# single-spi-interface.net
KiCad netlist of a schematic drawn in EAGLE
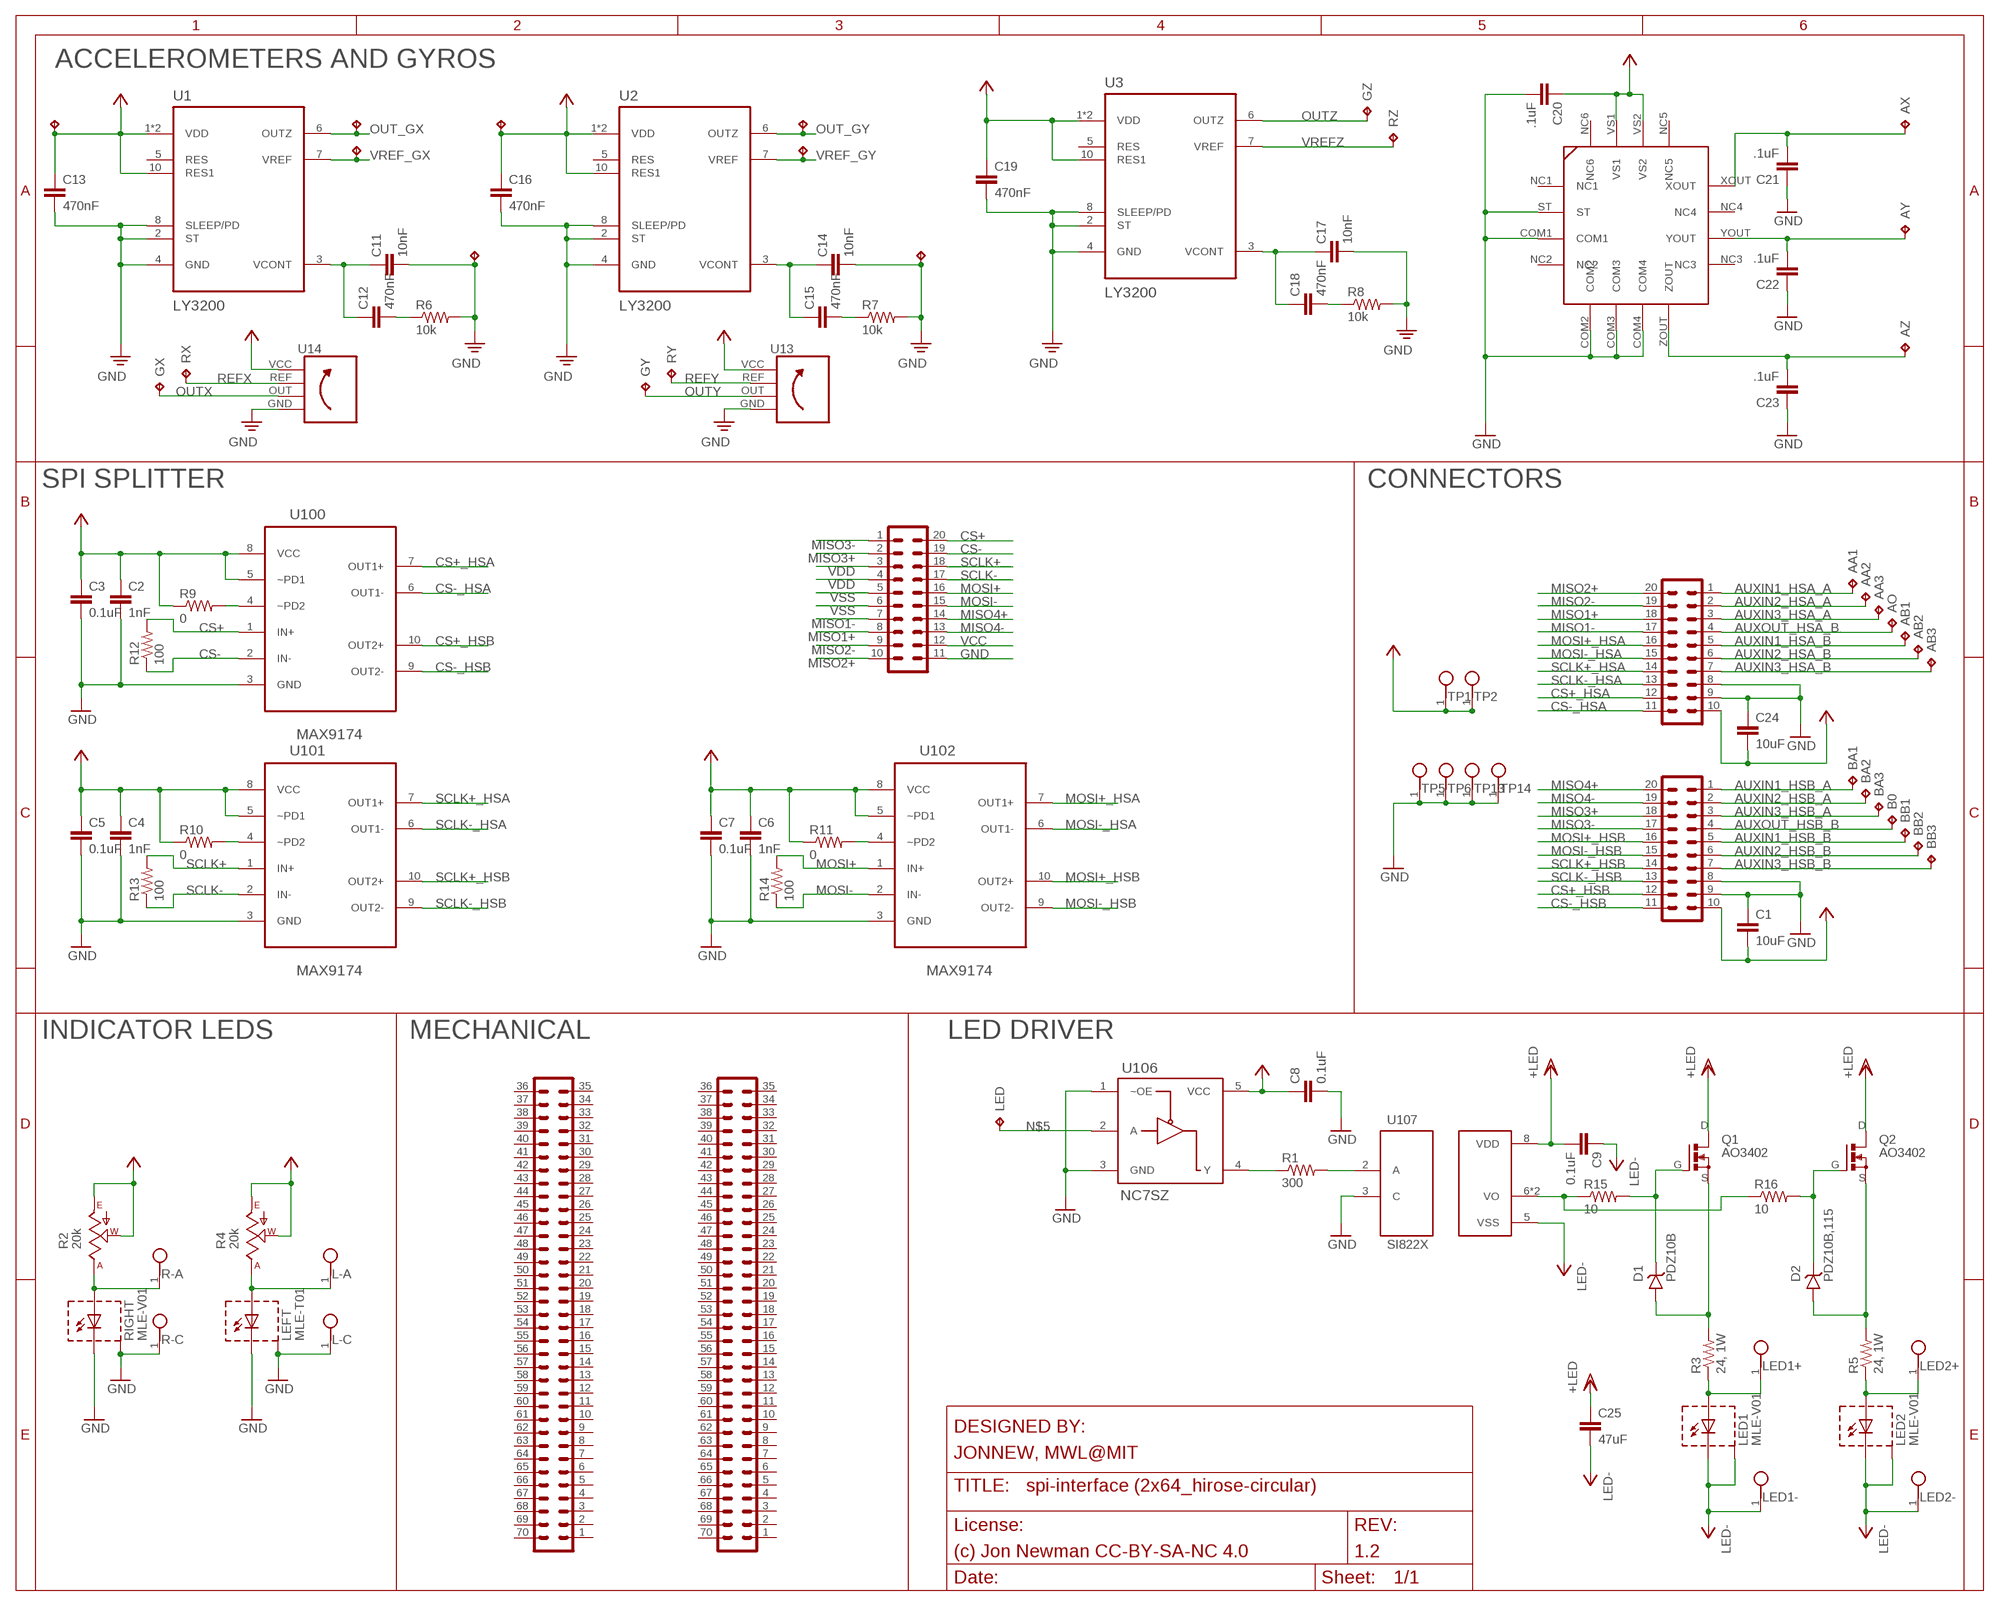
[diagram p0: schematic, sheet 1]

(export (version "E")
  (design (tool "Eeschema 10.0.6"))
  (components
    (comp (ref "AA1")
      (value "TP_0.5MM")
      (footprint "eagle-import:TESTPOINT_0.5MM")
      (libsource (lib "eagle-import") (part "TP_0.5MM"))
    )
    (comp (ref "AA2")
      (value "TP_0.5MM")
      (footprint "eagle-import:TESTPOINT_0.5MM")
      (libsource (lib "eagle-import") (part "TP_0.5MM"))
    )
    (comp (ref "AA3")
      (value "TP_0.5MM")
      (footprint "eagle-import:TESTPOINT_0.5MM")
      (libsource (lib "eagle-import") (part "TP_0.5MM"))
    )
    (comp (ref "AB1")
      (value "TP_0.5MM")
      (footprint "eagle-import:TESTPOINT_0.5MM")
      (libsource (lib "eagle-import") (part "TP_0.5MM"))
    )
    (comp (ref "AB2")
      (value "TP_0.5MM")
      (footprint "eagle-import:TESTPOINT_0.5MM")
      (libsource (lib "eagle-import") (part "TP_0.5MM"))
    )
    (comp (ref "AB3")
      (value "TP_0.5MM")
      (footprint "eagle-import:TESTPOINT_0.5MM")
      (libsource (lib "eagle-import") (part "TP_0.5MM"))
    )
    (comp (ref "AO")
      (value "TP_0.5MM")
      (footprint "eagle-import:TESTPOINT_0.5MM")
      (libsource (lib "eagle-import") (part "TP_0.5MM"))
    )
    (comp (ref "AX")
      (value "TP_0.5MM")
      (footprint "eagle-import:TESTPOINT_0.5MM")
      (libsource (lib "eagle-import") (part "TP_0.5MM"))
    )
    (comp (ref "AY")
      (value "TP_0.5MM")
      (footprint "eagle-import:TESTPOINT_0.5MM")
      (libsource (lib "eagle-import") (part "TP_0.5MM"))
    )
    (comp (ref "AZ")
      (value "TP_0.5MM")
      (footprint "eagle-import:TESTPOINT_0.5MM")
      (libsource (lib "eagle-import") (part "TP_0.5MM"))
    )
    (comp (ref "B0")
      (value "TP_0.5MM")
      (footprint "eagle-import:TESTPOINT_0.5MM")
      (libsource (lib "eagle-import") (part "TP_0.5MM"))
    )
    (comp (ref "BA1")
      (value "TP_0.5MM")
      (footprint "eagle-import:TESTPOINT_0.5MM")
      (libsource (lib "eagle-import") (part "TP_0.5MM"))
    )
    (comp (ref "BA2")
      (value "TP_0.5MM")
      (footprint "eagle-import:TESTPOINT_0.5MM")
      (libsource (lib "eagle-import") (part "TP_0.5MM"))
    )
    (comp (ref "BA3")
      (value "TP_0.5MM")
      (footprint "eagle-import:TESTPOINT_0.5MM")
      (libsource (lib "eagle-import") (part "TP_0.5MM"))
    )
    (comp (ref "BB1")
      (value "TP_0.5MM")
      (footprint "eagle-import:TESTPOINT_0.5MM")
      (libsource (lib "eagle-import") (part "TP_0.5MM"))
    )
    (comp (ref "BB2")
      (value "TP_0.5MM")
      (footprint "eagle-import:TESTPOINT_0.5MM")
      (libsource (lib "eagle-import") (part "TP_0.5MM"))
    )
    (comp (ref "BB3")
      (value "TP_0.5MM")
      (footprint "eagle-import:TESTPOINT_0.5MM")
      (libsource (lib "eagle-import") (part "TP_0.5MM"))
    )
    (comp (ref "C1")
      (value "10uF")
      (footprint "eagle-import:0805")
      (fields (field (name "PARTNO") "C2012X5R1Cxxxxxxx"))
      (libsource (lib "eagle-import") (part "C_0805"))
    )
    (comp (ref "C2")
      (value "1nF")
      (footprint "eagle-import:0201")
      (libsource (lib "eagle-import") (part "jonnew_C_0201"))
    )
    (comp (ref "C3")
      (value "0.1uF")
      (footprint "eagle-import:0402")
      (libsource (lib "eagle-import") (part "jonnew_C_0402"))
    )
    (comp (ref "C4")
      (value "1nF")
      (footprint "eagle-import:0201")
      (libsource (lib "eagle-import") (part "jonnew_C_0201"))
    )
    (comp (ref "C5")
      (value "0.1uF")
      (footprint "eagle-import:0402")
      (libsource (lib "eagle-import") (part "jonnew_C_0402"))
    )
    (comp (ref "C6")
      (value "1nF")
      (footprint "eagle-import:0201")
      (libsource (lib "eagle-import") (part "jonnew_C_0201"))
    )
    (comp (ref "C7")
      (value "0.1uF")
      (footprint "eagle-import:0402")
      (libsource (lib "eagle-import") (part "jonnew_C_0402"))
    )
    (comp (ref "C8")
      (value "0.1uF")
      (footprint "eagle-import:0402")
      (libsource (lib "eagle-import") (part "jonnew_C_0402"))
    )
    (comp (ref "C9")
      (value "0.1uF")
      (footprint "eagle-import:0402")
      (libsource (lib "eagle-import") (part "jonnew_C_0402"))
    )
    (comp (ref "C11")
      (value "10nF")
      (footprint "eagle-import:0201")
      (libsource (lib "eagle-import") (part "jonnew_C_0201"))
    )
    (comp (ref "C12")
      (value "470nF")
      (footprint "eagle-import:0201")
      (libsource (lib "eagle-import") (part "jonnew_C_0201"))
    )
    (comp (ref "C13")
      (value "470nF")
      (footprint "eagle-import:0201")
      (libsource (lib "eagle-import") (part "jonnew_C_0201"))
    )
    (comp (ref "C14")
      (value "10nF")
      (footprint "eagle-import:0201")
      (libsource (lib "eagle-import") (part "jonnew_C_0201"))
    )
    (comp (ref "C15")
      (value "470nF")
      (footprint "eagle-import:0201")
      (libsource (lib "eagle-import") (part "jonnew_C_0201"))
    )
    (comp (ref "C16")
      (value "470nF")
      (footprint "eagle-import:0201")
      (libsource (lib "eagle-import") (part "jonnew_C_0201"))
    )
    (comp (ref "C17")
      (value "10nF")
      (footprint "eagle-import:0201")
      (libsource (lib "eagle-import") (part "jonnew_C_0201"))
    )
    (comp (ref "C18")
      (value "470nF")
      (footprint "eagle-import:0201")
      (libsource (lib "eagle-import") (part "jonnew_C_0201"))
    )
    (comp (ref "C19")
      (value "470nF")
      (footprint "eagle-import:0201")
      (libsource (lib "eagle-import") (part "jonnew_C_0201"))
    )
    (comp (ref "C20")
      (value ".1uF")
      (footprint "eagle-import:0402")
      (libsource (lib "eagle-import") (part "C_0402"))
    )
    (comp (ref "C21")
      (value ".1uF")
      (footprint "eagle-import:0201")
      (libsource (lib "eagle-import") (part "jonnew_C_0201"))
    )
    (comp (ref "C22")
      (value ".1uF")
      (footprint "eagle-import:0201")
      (libsource (lib "eagle-import") (part "jonnew_C_0201"))
    )
    (comp (ref "C23")
      (value ".1uF")
      (footprint "eagle-import:0201")
      (libsource (lib "eagle-import") (part "jonnew_C_0201"))
    )
    (comp (ref "C24")
      (value "10uF")
      (footprint "eagle-import:0805")
      (fields (field (name "PARTNO") "C2012X5R1Cxxxxxxx"))
      (libsource (lib "eagle-import") (part "C_0805"))
    )
    (comp (ref "C25")
      (value "47uF")
      (footprint "eagle-import:1206")
      (libsource (lib "eagle-import") (part "jonnew_C_1206"))
    )
    (comp (ref "D1")
      (value "PDZ10B")
      (footprint "eagle-import:SOD-323")
      (libsource (lib "eagle-import") (part "Z-DIODE_SOD-323"))
    )
    (comp (ref "D2")
      (value "PDZ10B,115")
      (footprint "eagle-import:SOD-323")
      (libsource (lib "eagle-import") (part "Z-DIODE_SOD-323"))
    )
    (comp (ref "DIO_E1B")
      (value "PINHD-2X10_DF40-20REC")
      (footprint "eagle-import:DF40-20REC")
      (libsource (lib "eagle-import") (part "PINHD-2X10_DF40-20REC"))
    )
    (comp (ref "DIO_E1B1")
      (value "PINHD-2X10_DF40-20REC")
      (footprint "eagle-import:DF40-20REC")
      (libsource (lib "eagle-import") (part "PINHD-2X10_DF40-20REC"))
    )
    (comp (ref "GX")
      (value "TP_0.5MM")
      (footprint "eagle-import:TESTPOINT_0.5MM")
      (libsource (lib "eagle-import") (part "TP_0.5MM"))
    )
    (comp (ref "GY")
      (value "TP_0.5MM")
      (footprint "eagle-import:TESTPOINT_0.5MM")
      (libsource (lib "eagle-import") (part "TP_0.5MM"))
    )
    (comp (ref "GZ")
      (value "TP_0.5MM")
      (footprint "eagle-import:TESTPOINT_0.5MM")
      (libsource (lib "eagle-import") (part "TP_0.5MM"))
    )
    (comp (ref "L-A")
      (value "TESTPOINT_SMALL")
      (footprint "eagle-import:TESTPOINT_SMALL")
      (libsource (lib "eagle-import") (part "TESTPOINT_SMALL"))
    )
    (comp (ref "L-C")
      (value "TESTPOINT_SMALL")
      (footprint "eagle-import:TESTPOINT_SMALL")
      (libsource (lib "eagle-import") (part "TESTPOINT_SMALL"))
    )
    (comp (ref "LED")
      (value "TP_0.5MM")
      (footprint "eagle-import:TESTPOINT_0.5MM")
      (libsource (lib "eagle-import") (part "TP_0.5MM"))
    )
    (comp (ref "LED1")
      (value "MLE-V01")
      (footprint "eagle-import:LED-MLE")
      (libsource (lib "eagle-import") (part "LED_PKG-BODY"))
    )
    (comp (ref "LED1+")
      (value "TESTPOINT_SMALL")
      (footprint "eagle-import:TESTPOINT_SMALL")
      (libsource (lib "eagle-import") (part "TESTPOINT_SMALL"))
    )
    (comp (ref "LED1-")
      (value "TESTPOINT_SMALL")
      (footprint "eagle-import:TESTPOINT_SMALL")
      (libsource (lib "eagle-import") (part "TESTPOINT_SMALL"))
    )
    (comp (ref "LED2")
      (value "MLE-V01")
      (footprint "eagle-import:LED-MLE")
      (libsource (lib "eagle-import") (part "LED_PKG-BODY"))
    )
    (comp (ref "LED2+")
      (value "TESTPOINT_SMALL")
      (footprint "eagle-import:TESTPOINT_SMALL")
      (libsource (lib "eagle-import") (part "TESTPOINT_SMALL"))
    )
    (comp (ref "LED2-")
      (value "TESTPOINT_SMALL")
      (footprint "eagle-import:TESTPOINT_SMALL")
      (libsource (lib "eagle-import") (part "TESTPOINT_SMALL"))
    )
    (comp (ref "LEFT")
      (value "MLE-T01")
      (footprint "eagle-import:LED-MLE")
      (libsource (lib "eagle-import") (part "LED_PKG-BODY"))
    )
    (comp (ref "MECH_E0B")
      (value "PINHD-2X35_DF40REC")
      (footprint "eagle-import:DF40-70REC")
      (libsource (lib "eagle-import") (part "PINHD-2X35_DF40REC"))
    )
    (comp (ref "MECH_W0B")
      (value "PINHD-2X35_DF40REC")
      (footprint "eagle-import:DF40-70REC")
      (libsource (lib "eagle-import") (part "PINHD-2X35_DF40REC"))
    )
    (comp (ref "Q1")
      (value "AO3402")
      (footprint "eagle-import:SOT23-GSD")
      (libsource (lib "eagle-import") (part "N-MOSFET_SOT23-GSD"))
    )
    (comp (ref "Q2")
      (value "AO3402")
      (footprint "eagle-import:SOT23-GSD")
      (libsource (lib "eagle-import") (part "N-MOSFET_SOT23-GSD"))
    )
    (comp (ref "R-A")
      (value "TESTPOINT_SMALL")
      (footprint "eagle-import:TESTPOINT_SMALL")
      (libsource (lib "eagle-import") (part "TESTPOINT_SMALL"))
    )
    (comp (ref "R-C")
      (value "TESTPOINT_SMALL")
      (footprint "eagle-import:TESTPOINT_SMALL")
      (libsource (lib "eagle-import") (part "TESTPOINT_SMALL"))
    )
    (comp (ref "R1")
      (value "300")
      (footprint "eagle-import:0402")
      (libsource (lib "eagle-import") (part "R_0402"))
    )
    (comp (ref "R2")
      (value "20k")
      (footprint "eagle-import:SM-42_43W")
      (libsource (lib "eagle-import") (part "TRIM_US-SM-42/43W"))
    )
    (comp (ref "R3")
      (value "24, 1W")
      (footprint "eagle-import:0805")
      (libsource (lib "eagle-import") (part "R_0805"))
    )
    (comp (ref "R4")
      (value "20k")
      (footprint "eagle-import:SM-42_43W")
      (libsource (lib "eagle-import") (part "TRIM_US-SM-42/43W"))
    )
    (comp (ref "R5")
      (value "24, 1W")
      (footprint "eagle-import:0805")
      (libsource (lib "eagle-import") (part "R_0805"))
    )
    (comp (ref "R6")
      (value "10k")
      (footprint "eagle-import:0201")
      (libsource (lib "eagle-import") (part "R_0201"))
    )
    (comp (ref "R7")
      (value "10k")
      (footprint "eagle-import:0201")
      (libsource (lib "eagle-import") (part "R_0201"))
    )
    (comp (ref "R8")
      (value "10k")
      (footprint "eagle-import:0201")
      (libsource (lib "eagle-import") (part "R_0201"))
    )
    (comp (ref "R9")
      (value "0")
      (footprint "eagle-import:0201")
      (libsource (lib "eagle-import") (part "R_0201"))
    )
    (comp (ref "R10")
      (value "0")
      (footprint "eagle-import:0201")
      (libsource (lib "eagle-import") (part "R_0201"))
    )
    (comp (ref "R11")
      (value "0")
      (footprint "eagle-import:0201")
      (libsource (lib "eagle-import") (part "R_0201"))
    )
    (comp (ref "R12")
      (value "100")
      (footprint "eagle-import:0201")
      (libsource (lib "eagle-import") (part "R_0201"))
    )
    (comp (ref "R13")
      (value "100")
      (footprint "eagle-import:0201")
      (libsource (lib "eagle-import") (part "R_0201"))
    )
    (comp (ref "R14")
      (value "100")
      (footprint "eagle-import:0201")
      (libsource (lib "eagle-import") (part "R_0201"))
    )
    (comp (ref "R15")
      (value "10")
      (footprint "eagle-import:0402")
      (libsource (lib "eagle-import") (part "R_0402"))
    )
    (comp (ref "R16")
      (value "10")
      (footprint "eagle-import:0402")
      (libsource (lib "eagle-import") (part "R_0402"))
    )
    (comp (ref "RIGHT")
      (value "MLE-V01")
      (footprint "eagle-import:LED-MLE")
      (libsource (lib "eagle-import") (part "LED_PKG-BODY"))
    )
    (comp (ref "RX")
      (value "TP_0.5MM")
      (footprint "eagle-import:TESTPOINT_0.5MM")
      (libsource (lib "eagle-import") (part "TP_0.5MM"))
    )
    (comp (ref "RY")
      (value "TP_0.5MM")
      (footprint "eagle-import:TESTPOINT_0.5MM")
      (libsource (lib "eagle-import") (part "TP_0.5MM"))
    )
    (comp (ref "RZ")
      (value "TP_0.5MM")
      (footprint "eagle-import:TESTPOINT_0.5MM")
      (libsource (lib "eagle-import") (part "TP_0.5MM"))
    )
    (comp (ref "TETHER")
      (value "PINHD-2X10_T1M")
      (footprint "eagle-import:T1M-10-T-DV")
      (libsource (lib "eagle-import") (part "PINHD-2X10_T1M"))
    )
    (comp (ref "TP1")
      (value "TESTPOINT_SMALL")
      (footprint "eagle-import:TESTPOINT_SMALL")
      (libsource (lib "eagle-import") (part "TESTPOINT_SMALL"))
    )
    (comp (ref "TP2")
      (value "TESTPOINT_SMALL")
      (footprint "eagle-import:TESTPOINT_SMALL")
      (libsource (lib "eagle-import") (part "TESTPOINT_SMALL"))
    )
    (comp (ref "TP3")
      (value "TPTP08SQ")
      (footprint "eagle-import:TP08SQ")
      (libsource (lib "eagle-import") (part "TPTP08SQ"))
    )
    (comp (ref "TP4")
      (value "TPTP08SQ")
      (footprint "eagle-import:TP08SQ")
      (libsource (lib "eagle-import") (part "TPTP08SQ"))
    )
    (comp (ref "TP5")
      (value "TESTPOINT_SMALL")
      (footprint "eagle-import:TESTPOINT_SMALL")
      (libsource (lib "eagle-import") (part "TESTPOINT_SMALL"))
    )
    (comp (ref "TP6")
      (value "TESTPOINT_SMALL")
      (footprint "eagle-import:TESTPOINT_SMALL")
      (libsource (lib "eagle-import") (part "TESTPOINT_SMALL"))
    )
    (comp (ref "TP7")
      (value "TPTP08SQ")
      (footprint "eagle-import:TP08SQ")
      (libsource (lib "eagle-import") (part "TPTP08SQ"))
    )
    (comp (ref "TP8")
      (value "TPTP08SQ")
      (footprint "eagle-import:TP08SQ")
      (libsource (lib "eagle-import") (part "TPTP08SQ"))
    )
    (comp (ref "TP9")
      (value "TPTP08SQ")
      (footprint "eagle-import:TP08SQ")
      (libsource (lib "eagle-import") (part "TPTP08SQ"))
    )
    (comp (ref "TP10")
      (value "TPTP08SQ")
      (footprint "eagle-import:TP08SQ")
      (libsource (lib "eagle-import") (part "TPTP08SQ"))
    )
    (comp (ref "TP11")
      (value "TPTP08SQ")
      (footprint "eagle-import:TP08SQ")
      (libsource (lib "eagle-import") (part "TPTP08SQ"))
    )
    (comp (ref "TP12")
      (value "TPTP08SQ")
      (footprint "eagle-import:TP08SQ")
      (libsource (lib "eagle-import") (part "TPTP08SQ"))
    )
    (comp (ref "TP13")
      (value "TESTPOINT_SMALL")
      (footprint "eagle-import:TESTPOINT_SMALL")
      (libsource (lib "eagle-import") (part "TESTPOINT_SMALL"))
    )
    (comp (ref "TP14")
      (value "TESTPOINT_SMALL")
      (footprint "eagle-import:TESTPOINT_SMALL")
      (libsource (lib "eagle-import") (part "TESTPOINT_SMALL"))
    )
    (comp (ref "U1")
      (value "LY3200")
      (footprint "eagle-import:LGA-10-COMPACT")
      (libsource (lib "eagle-import") (part "LY3200ALH_LGA-10-COMPACT"))
    )
    (comp (ref "U2")
      (value "LY3200")
      (footprint "eagle-import:LGA-10-COMPACT")
      (libsource (lib "eagle-import") (part "LY3200ALH_LGA-10-COMPACT"))
    )
    (comp (ref "U3")
      (value "LY3200")
      (footprint "eagle-import:LGA-10-COMPACT")
      (libsource (lib "eagle-import") (part "LY3200ALH_LGA-10-COMPACT"))
    )
    (comp (ref "U4")
      (value "ADXL335")
      (footprint "eagle-import:ADXL335")
      (libsource (lib "eagle-import") (part "ADXL335"))
    )
    (comp (ref "U13")
      (value "LY3200-VERT-MODULE")
      (footprint "eagle-import:LY3200-VERT-MODULE")
      (libsource (lib "eagle-import") (part "LY3200-VERT-MODULE"))
    )
    (comp (ref "U14")
      (value "LY3200-VERT-MODULE")
      (footprint "eagle-import:LY3200-VERT-MODULE")
      (libsource (lib "eagle-import") (part "LY3200-VERT-MODULE"))
    )
    (comp (ref "U100")
      (value "MAX9174")
      (footprint "eagle-import:10-UMAX")
      (libsource (lib "eagle-import") (part "MAX9174_UMAX"))
    )
    (comp (ref "U101")
      (value "MAX9174")
      (footprint "eagle-import:10-UMAX")
      (libsource (lib "eagle-import") (part "MAX9174_UMAX"))
    )
    (comp (ref "U102")
      (value "MAX9174")
      (footprint "eagle-import:10-UMAX")
      (libsource (lib "eagle-import") (part "MAX9174_UMAX"))
    )
    (comp (ref "U106")
      (value "NC7SZ")
      (footprint "eagle-import:SOT-23-5")
      (libsource (lib "eagle-import") (part "NC7SZ125"))
    )
    (comp (ref "U107")
      (value "SI822X")
      (footprint "eagle-import:SOIC127P500X400-8N")
      (libsource (lib "eagle-import") (part "SI822X"))
    )
  )
  (nets
    (net (code "1") (name "+LED") (class "Default")
      (node (ref "C25") (pin "1") (pinfunction "1_1") (pintype "passive"))
      (node (ref "C9") (pin "2") (pinfunction "2_2") (pintype "passive"))
      (node (ref "Q1") (pin "D") (pinfunction "D_D") (pintype "bidirectional"))
      (node (ref "Q2") (pin "D") (pinfunction "D_D") (pintype "bidirectional"))
      (node (ref "TETHER") (pin "3") (pinfunction "3_3") (pintype "bidirectional"))
      (node (ref "TETHER") (pin "4") (pinfunction "4_4") (pintype "bidirectional"))
      (node (ref "U107") (pin "8") (pinfunction "VDD_8") (pintype "power_in"))
    )
    (net (code "2") (name "/AUXIN1_HSA_A") (class "Default")
      (node (ref "AA1") (pin "1") (pinfunction "TP_1") (pintype "input"))
      (node (ref "DIO_E1B") (pin "1") (pinfunction "1_1") (pintype "bidirectional"))
    )
    (net (code "3") (name "/AUXIN1_HSA_B") (class "Default")
      (node (ref "AB1") (pin "1") (pinfunction "TP_1") (pintype "input"))
      (node (ref "DIO_E1B") (pin "5") (pinfunction "5_5") (pintype "bidirectional"))
    )
    (net (code "4") (name "/AUXIN1_HSB_A") (class "Default")
      (node (ref "BA1") (pin "1") (pinfunction "TP_1") (pintype "input"))
      (node (ref "DIO_E1B1") (pin "1") (pinfunction "1_1") (pintype "bidirectional"))
    )
    (net (code "5") (name "/AUXIN1_HSB_B") (class "Default")
      (node (ref "BB1") (pin "1") (pinfunction "TP_1") (pintype "input"))
      (node (ref "DIO_E1B1") (pin "5") (pinfunction "5_5") (pintype "bidirectional"))
    )
    (net (code "6") (name "/AUXIN2_HSA_A") (class "Default")
      (node (ref "AA2") (pin "1") (pinfunction "TP_1") (pintype "input"))
      (node (ref "DIO_E1B") (pin "2") (pinfunction "2_2") (pintype "bidirectional"))
    )
    (net (code "7") (name "/AUXIN2_HSA_B") (class "Default")
      (node (ref "AB2") (pin "1") (pinfunction "TP_1") (pintype "input"))
      (node (ref "DIO_E1B") (pin "6") (pinfunction "6_6") (pintype "bidirectional"))
    )
    (net (code "8") (name "/AUXIN2_HSB_A") (class "Default")
      (node (ref "BA2") (pin "1") (pinfunction "TP_1") (pintype "input"))
      (node (ref "DIO_E1B1") (pin "2") (pinfunction "2_2") (pintype "bidirectional"))
    )
    (net (code "9") (name "/AUXIN2_HSB_B") (class "Default")
      (node (ref "BB2") (pin "1") (pinfunction "TP_1") (pintype "input"))
      (node (ref "DIO_E1B1") (pin "6") (pinfunction "6_6") (pintype "bidirectional"))
    )
    (net (code "10") (name "/AUXIN3_HSA_A") (class "Default")
      (node (ref "AA3") (pin "1") (pinfunction "TP_1") (pintype "input"))
      (node (ref "DIO_E1B") (pin "3") (pinfunction "3_3") (pintype "bidirectional"))
    )
    (net (code "11") (name "/AUXIN3_HSA_B") (class "Default")
      (node (ref "AB3") (pin "1") (pinfunction "TP_1") (pintype "input"))
      (node (ref "DIO_E1B") (pin "7") (pinfunction "7_7") (pintype "bidirectional"))
    )
    (net (code "12") (name "/AUXIN3_HSB_A") (class "Default")
      (node (ref "BA3") (pin "1") (pinfunction "TP_1") (pintype "input"))
      (node (ref "DIO_E1B1") (pin "3") (pinfunction "3_3") (pintype "bidirectional"))
    )
    (net (code "13") (name "/AUXIN3_HSB_B") (class "Default")
      (node (ref "BB3") (pin "1") (pinfunction "TP_1") (pintype "input"))
      (node (ref "DIO_E1B1") (pin "7") (pinfunction "7_7") (pintype "bidirectional"))
    )
    (net (code "14") (name "/AUXOUT_HSA_B") (class "Default")
      (node (ref "AO") (pin "1") (pinfunction "TP_1") (pintype "input"))
      (node (ref "DIO_E1B") (pin "4") (pinfunction "4_4") (pintype "bidirectional"))
    )
    (net (code "15") (name "/AUXOUT_HSB_B") (class "Default")
      (node (ref "B0") (pin "1") (pinfunction "TP_1") (pintype "input"))
      (node (ref "DIO_E1B1") (pin "4") (pinfunction "4_4") (pintype "bidirectional"))
    )
    (net (code "16") (name "/CS+") (class "Default")
      (node (ref "R12") (pin "2") (pinfunction "2_2") (pintype "passive"))
      (node (ref "TETHER") (pin "20") (pinfunction "20_20") (pintype "bidirectional"))
      (node (ref "U100") (pin "1") (pinfunction "IN+_1") (pintype "input"))
    )
    (net (code "17") (name "/CS+_HSA") (class "Default")
      (node (ref "DIO_E1B") (pin "12") (pinfunction "12_12") (pintype "bidirectional"))
      (node (ref "U100") (pin "7") (pinfunction "OUT1+_7") (pintype "output"))
    )
    (net (code "18") (name "/CS+_HSB") (class "Default")
      (node (ref "DIO_E1B1") (pin "12") (pinfunction "12_12") (pintype "bidirectional"))
      (node (ref "U100") (pin "10") (pinfunction "OUT2+_10") (pintype "output"))
    )
    (net (code "19") (name "/CS-") (class "Default")
      (node (ref "R12") (pin "1") (pinfunction "1_1") (pintype "passive"))
      (node (ref "TETHER") (pin "19") (pinfunction "19_19") (pintype "bidirectional"))
      (node (ref "U100") (pin "2") (pinfunction "IN-_2") (pintype "input"))
    )
    (net (code "20") (name "/CS-_HSA") (class "Default")
      (node (ref "DIO_E1B") (pin "11") (pinfunction "11_11") (pintype "bidirectional"))
      (node (ref "U100") (pin "6") (pinfunction "OUT1-_6") (pintype "output"))
    )
    (net (code "21") (name "/CS-_HSB") (class "Default")
      (node (ref "DIO_E1B1") (pin "11") (pinfunction "11_11") (pintype "bidirectional"))
      (node (ref "U100") (pin "9") (pinfunction "OUT2-_9") (pintype "output"))
    )
    (net (code "22") (name "/MISO1+") (class "Default")
      (node (ref "DIO_E1B") (pin "18") (pinfunction "18_18") (pintype "bidirectional"))
      (node (ref "TETHER") (pin "8") (pinfunction "8_8") (pintype "bidirectional"))
    )
    (net (code "23") (name "/MISO1-") (class "Default")
      (node (ref "DIO_E1B") (pin "17") (pinfunction "17_17") (pintype "bidirectional"))
      (node (ref "TETHER") (pin "7") (pinfunction "7_7") (pintype "bidirectional"))
    )
    (net (code "24") (name "/MISO2+") (class "Default")
      (node (ref "DIO_E1B") (pin "20") (pinfunction "20_20") (pintype "bidirectional"))
      (node (ref "TETHER") (pin "10") (pinfunction "10_10") (pintype "bidirectional"))
    )
    (net (code "25") (name "/MISO2-") (class "Default")
      (node (ref "DIO_E1B") (pin "19") (pinfunction "19_19") (pintype "bidirectional"))
      (node (ref "TETHER") (pin "9") (pinfunction "9_9") (pintype "bidirectional"))
    )
    (net (code "26") (name "/MISO3+") (class "Default")
      (node (ref "DIO_E1B1") (pin "18") (pinfunction "18_18") (pintype "bidirectional"))
      (node (ref "TETHER") (pin "2") (pinfunction "2_2") (pintype "bidirectional"))
    )
    (net (code "27") (name "/MISO3-") (class "Default")
      (node (ref "DIO_E1B1") (pin "17") (pinfunction "17_17") (pintype "bidirectional"))
      (node (ref "TETHER") (pin "1") (pinfunction "1_1") (pintype "bidirectional"))
    )
    (net (code "28") (name "/MISO4+") (class "Default")
      (node (ref "DIO_E1B1") (pin "20") (pinfunction "20_20") (pintype "bidirectional"))
      (node (ref "TETHER") (pin "14") (pinfunction "14_14") (pintype "bidirectional"))
    )
    (net (code "29") (name "/MISO4-") (class "Default")
      (node (ref "DIO_E1B1") (pin "19") (pinfunction "19_19") (pintype "bidirectional"))
      (node (ref "TETHER") (pin "13") (pinfunction "13_13") (pintype "bidirectional"))
    )
    (net (code "30") (name "/MOSI+") (class "Default")
      (node (ref "R14") (pin "2") (pinfunction "2_2") (pintype "passive"))
      (node (ref "TETHER") (pin "16") (pinfunction "16_16") (pintype "bidirectional"))
      (node (ref "U102") (pin "1") (pinfunction "IN+_1") (pintype "input"))
    )
    (net (code "31") (name "/MOSI+_HSA") (class "Default")
      (node (ref "DIO_E1B") (pin "16") (pinfunction "16_16") (pintype "bidirectional"))
      (node (ref "U102") (pin "7") (pinfunction "OUT1+_7") (pintype "output"))
    )
    (net (code "32") (name "/MOSI+_HSB") (class "Default")
      (node (ref "DIO_E1B1") (pin "16") (pinfunction "16_16") (pintype "bidirectional"))
      (node (ref "U102") (pin "10") (pinfunction "OUT2+_10") (pintype "output"))
    )
    (net (code "33") (name "/MOSI-") (class "Default")
      (node (ref "R14") (pin "1") (pinfunction "1_1") (pintype "passive"))
      (node (ref "TETHER") (pin "15") (pinfunction "15_15") (pintype "bidirectional"))
      (node (ref "U102") (pin "2") (pinfunction "IN-_2") (pintype "input"))
    )
    (net (code "34") (name "/MOSI-_HSA") (class "Default")
      (node (ref "DIO_E1B") (pin "15") (pinfunction "15_15") (pintype "bidirectional"))
      (node (ref "U102") (pin "6") (pinfunction "OUT1-_6") (pintype "output"))
    )
    (net (code "35") (name "/MOSI-_HSB") (class "Default")
      (node (ref "DIO_E1B1") (pin "15") (pinfunction "15_15") (pintype "bidirectional"))
      (node (ref "U102") (pin "9") (pinfunction "OUT2-_9") (pintype "output"))
    )
    (net (code "36") (name "/N$5") (class "Default")
      (node (ref "LED") (pin "1") (pinfunction "TP_1") (pintype "input"))
      (node (ref "U106") (pin "2") (pinfunction "A_2") (pintype "input"))
    )
    (net (code "37") (name "/OUTX") (class "Default")
      (node (ref "GX") (pin "1") (pinfunction "TP_1") (pintype "input"))
      (node (ref "U14") (pin "OUT") (pinfunction "OUT_OUT") (pintype "output"))
    )
    (net (code "38") (name "/OUTY") (class "Default")
      (node (ref "GY") (pin "1") (pinfunction "TP_1") (pintype "input"))
      (node (ref "U13") (pin "OUT") (pinfunction "OUT_OUT") (pintype "output"))
    )
    (net (code "39") (name "/OUTZ") (class "Default")
      (node (ref "GZ") (pin "1") (pinfunction "TP_1") (pintype "input"))
      (node (ref "U3") (pin "6") (pinfunction "OUTZ_6") (pintype "output"))
    )
    (net (code "40") (name "/OUT_GX") (class "Default")
      (node (ref "TP4") (pin "TP") (pinfunction "TP_TP") (pintype "input"))
      (node (ref "U1") (pin "6") (pinfunction "OUTZ_6") (pintype "output"))
    )
    (net (code "41") (name "/OUT_GY") (class "Default")
      (node (ref "TP10") (pin "TP") (pinfunction "TP_TP") (pintype "input"))
      (node (ref "U2") (pin "6") (pinfunction "OUTZ_6") (pintype "output"))
    )
    (net (code "42") (name "/REFX") (class "Default")
      (node (ref "RX") (pin "1") (pinfunction "TP_1") (pintype "input"))
      (node (ref "U14") (pin "REF") (pinfunction "REF_REF") (pintype "output"))
    )
    (net (code "43") (name "/REFY") (class "Default")
      (node (ref "RY") (pin "1") (pinfunction "TP_1") (pintype "input"))
      (node (ref "U13") (pin "REF") (pinfunction "REF_REF") (pintype "output"))
    )
    (net (code "44") (name "/SCLK+") (class "Default")
      (node (ref "R13") (pin "2") (pinfunction "2_2") (pintype "passive"))
      (node (ref "TETHER") (pin "18") (pinfunction "18_18") (pintype "bidirectional"))
      (node (ref "U101") (pin "1") (pinfunction "IN+_1") (pintype "input"))
    )
    (net (code "45") (name "/SCLK+_HSA") (class "Default")
      (node (ref "DIO_E1B") (pin "14") (pinfunction "14_14") (pintype "bidirectional"))
      (node (ref "U101") (pin "7") (pinfunction "OUT1+_7") (pintype "output"))
    )
    (net (code "46") (name "/SCLK+_HSB") (class "Default")
      (node (ref "DIO_E1B1") (pin "14") (pinfunction "14_14") (pintype "bidirectional"))
      (node (ref "U101") (pin "10") (pinfunction "OUT2+_10") (pintype "output"))
    )
    (net (code "47") (name "/SCLK-") (class "Default")
      (node (ref "R13") (pin "1") (pinfunction "1_1") (pintype "passive"))
      (node (ref "TETHER") (pin "17") (pinfunction "17_17") (pintype "bidirectional"))
      (node (ref "U101") (pin "2") (pinfunction "IN-_2") (pintype "input"))
    )
    (net (code "48") (name "/SCLK-_HSA") (class "Default")
      (node (ref "DIO_E1B") (pin "13") (pinfunction "13_13") (pintype "bidirectional"))
      (node (ref "U101") (pin "6") (pinfunction "OUT1-_6") (pintype "output"))
    )
    (net (code "49") (name "/SCLK-_HSB") (class "Default")
      (node (ref "DIO_E1B1") (pin "13") (pinfunction "13_13") (pintype "bidirectional"))
      (node (ref "U101") (pin "9") (pinfunction "OUT2-_9") (pintype "output"))
    )
    (net (code "50") (name "/VREFZ") (class "Default")
      (node (ref "RZ") (pin "1") (pinfunction "TP_1") (pintype "input"))
      (node (ref "U3") (pin "7") (pinfunction "VREF_7") (pintype "output"))
    )
    (net (code "51") (name "/VREF_GX") (class "Default")
      (node (ref "TP8") (pin "TP") (pinfunction "TP_TP") (pintype "input"))
      (node (ref "U1") (pin "7") (pinfunction "VREF_7") (pintype "output"))
    )
    (net (code "52") (name "/VREF_GY") (class "Default")
      (node (ref "TP12") (pin "TP") (pinfunction "TP_TP") (pintype "input"))
      (node (ref "U2") (pin "7") (pinfunction "VREF_7") (pintype "output"))
    )
    (net (code "53") (name "GND") (class "Default")
      (node (ref "C1") (pin "1") (pinfunction "1_1") (pintype "passive"))
      (node (ref "C11") (pin "2") (pinfunction "2_2") (pintype "passive"))
      (node (ref "C13") (pin "2") (pinfunction "2_2") (pintype "passive"))
      (node (ref "C14") (pin "2") (pinfunction "2_2") (pintype "passive"))
      (node (ref "C16") (pin "2") (pinfunction "2_2") (pintype "passive"))
      (node (ref "C17") (pin "2") (pinfunction "2_2") (pintype "passive"))
      (node (ref "C19") (pin "2") (pinfunction "2_2") (pintype "passive"))
      (node (ref "C2") (pin "2") (pinfunction "2_2") (pintype "passive"))
      (node (ref "C20") (pin "2") (pinfunction "2_2") (pintype "passive"))
      (node (ref "C21") (pin "1") (pinfunction "1_1") (pintype "passive"))
      (node (ref "C22") (pin "1") (pinfunction "1_1") (pintype "passive"))
      (node (ref "C23") (pin "1") (pinfunction "1_1") (pintype "passive"))
      (node (ref "C24") (pin "1") (pinfunction "1_1") (pintype "passive"))
      (node (ref "C3") (pin "2") (pinfunction "2_2") (pintype "passive"))
      (node (ref "C4") (pin "2") (pinfunction "2_2") (pintype "passive"))
      (node (ref "C5") (pin "2") (pinfunction "2_2") (pintype "passive"))
      (node (ref "C6") (pin "2") (pinfunction "2_2") (pintype "passive"))
      (node (ref "C7") (pin "2") (pinfunction "2_2") (pintype "passive"))
      (node (ref "C8") (pin "2") (pinfunction "2_2") (pintype "passive"))
      (node (ref "DIO_E1B") (pin "8") (pinfunction "8_8") (pintype "bidirectional"))
      (node (ref "DIO_E1B") (pin "9") (pinfunction "9_9") (pintype "bidirectional"))
      (node (ref "DIO_E1B1") (pin "8") (pinfunction "8_8") (pintype "bidirectional"))
      (node (ref "DIO_E1B1") (pin "9") (pinfunction "9_9") (pintype "bidirectional"))
      (node (ref "L-C") (pin "1") (pinfunction "1_1") (pintype "passive"))
      (node (ref "LEFT") (pin "C1") (pinfunction "C_C1") (pintype "passive"))
      (node (ref "LEFT") (pin "C2") (pinfunction "C_C2") (pintype "passive"))
      (node (ref "LEFT") (pin "HS") (pinfunction "BODY_HS") (pintype "passive"))
      (node (ref "R-C") (pin "1") (pinfunction "1_1") (pintype "passive"))
      (node (ref "R6") (pin "2") (pinfunction "2_2") (pintype "passive"))
      (node (ref "R7") (pin "2") (pinfunction "2_2") (pintype "passive"))
      (node (ref "R8") (pin "2") (pinfunction "2_2") (pintype "passive"))
      (node (ref "RIGHT") (pin "C1") (pinfunction "C_C1") (pintype "passive"))
      (node (ref "RIGHT") (pin "C2") (pinfunction "C_C2") (pintype "passive"))
      (node (ref "RIGHT") (pin "HS") (pinfunction "BODY_HS") (pintype "passive"))
      (node (ref "TETHER") (pin "11") (pinfunction "11_11") (pintype "bidirectional"))
      (node (ref "TP11") (pin "TP") (pinfunction "TP_TP") (pintype "input"))
      (node (ref "TP13") (pin "1") (pinfunction "1_1") (pintype "passive"))
      (node (ref "TP14") (pin "1") (pinfunction "1_1") (pintype "passive"))
      (node (ref "TP5") (pin "1") (pinfunction "1_1") (pintype "passive"))
      (node (ref "TP6") (pin "1") (pinfunction "1_1") (pintype "passive"))
      (node (ref "TP7") (pin "TP") (pinfunction "TP_TP") (pintype "input"))
      (node (ref "U1") (pin "2") (pinfunction "ST_2") (pintype "bidirectional"))
      (node (ref "U1") (pin "4") (pinfunction "GND_4") (pintype "power_in"))
      (node (ref "U1") (pin "8") (pinfunction "SLEEP/PD_8") (pintype "bidirectional"))
      (node (ref "U100") (pin "3") (pinfunction "GND_3") (pintype "power_in"))
      (node (ref "U101") (pin "3") (pinfunction "GND_3") (pintype "power_in"))
      (node (ref "U102") (pin "3") (pinfunction "GND_3") (pintype "power_in"))
      (node (ref "U106") (pin "1") (pinfunction "~{OE}_1") (pintype "input"))
      (node (ref "U106") (pin "3") (pinfunction "GND_3") (pintype "power_in"))
      (node (ref "U107") (pin "3") (pinfunction "C_3") (pintype "bidirectional"))
      (node (ref "U13") (pin "GND") (pinfunction "GND_GND") (pintype "power_in"))
      (node (ref "U14") (pin "GND") (pinfunction "GND_GND") (pintype "power_in"))
      (node (ref "U2") (pin "2") (pinfunction "ST_2") (pintype "bidirectional"))
      (node (ref "U2") (pin "4") (pinfunction "GND_4") (pintype "power_in"))
      (node (ref "U2") (pin "8") (pinfunction "SLEEP/PD_8") (pintype "bidirectional"))
      (node (ref "U3") (pin "2") (pinfunction "ST_2") (pintype "bidirectional"))
      (node (ref "U3") (pin "4") (pinfunction "GND_4") (pintype "power_in"))
      (node (ref "U3") (pin "8") (pinfunction "SLEEP/PD_8") (pintype "bidirectional"))
      (node (ref "U4") (pin "COM1") (pinfunction "COM1_COM1") (pintype "bidirectional"))
      (node (ref "U4") (pin "COM2") (pinfunction "COM2_COM2") (pintype "bidirectional"))
      (node (ref "U4") (pin "COM3") (pinfunction "COM3_COM3") (pintype "bidirectional"))
      (node (ref "U4") (pin "COM4") (pinfunction "COM4_COM4") (pintype "bidirectional"))
      (node (ref "U4") (pin "ST") (pinfunction "ST_ST") (pintype "bidirectional"))
    )
    (net (code "54") (name "LED-") (class "Default")
      (node (ref "C25") (pin "2") (pinfunction "2_2") (pintype "passive"))
      (node (ref "C9") (pin "1") (pinfunction "1_1") (pintype "passive"))
      (node (ref "LED1") (pin "C1") (pinfunction "C_C1") (pintype "passive"))
      (node (ref "LED1") (pin "C2") (pinfunction "C_C2") (pintype "passive"))
      (node (ref "LED1") (pin "HS") (pinfunction "BODY_HS") (pintype "passive"))
      (node (ref "LED1-") (pin "1") (pinfunction "1_1") (pintype "passive"))
      (node (ref "LED2") (pin "C1") (pinfunction "C_C1") (pintype "passive"))
      (node (ref "LED2") (pin "C2") (pinfunction "C_C2") (pintype "passive"))
      (node (ref "LED2") (pin "HS") (pinfunction "BODY_HS") (pintype "passive"))
      (node (ref "LED2-") (pin "1") (pinfunction "1_1") (pintype "passive"))
      (node (ref "TETHER") (pin "5") (pinfunction "5_5") (pintype "bidirectional"))
      (node (ref "TETHER") (pin "6") (pinfunction "6_6") (pintype "bidirectional"))
      (node (ref "U107") (pin "5") (pinfunction "VSS_5") (pintype "power_in"))
    )
    (net (code "55") (name "Net-(AX-TP)") (class "Default")
      (node (ref "AX") (pin "1") (pinfunction "TP_1") (pintype "input"))
      (node (ref "C21") (pin "2") (pinfunction "2_2") (pintype "passive"))
      (node (ref "U4") (pin "XOUT") (pinfunction "XOUT_XOUT") (pintype "bidirectional"))
    )
    (net (code "56") (name "Net-(AY-TP)") (class "Default")
      (node (ref "AY") (pin "1") (pinfunction "TP_1") (pintype "input"))
      (node (ref "C22") (pin "2") (pinfunction "2_2") (pintype "passive"))
      (node (ref "U4") (pin "YOUT") (pinfunction "YOUT_YOUT") (pintype "bidirectional"))
    )
    (net (code "57") (name "Net-(AZ-TP)") (class "Default")
      (node (ref "AZ") (pin "1") (pinfunction "TP_1") (pintype "input"))
      (node (ref "C23") (pin "2") (pinfunction "2_2") (pintype "passive"))
      (node (ref "U4") (pin "ZOUT") (pinfunction "ZOUT_ZOUT") (pintype "bidirectional"))
    )
    (net (code "58") (name "Net-(C12-Pad2)") (class "Default")
      (node (ref "C12") (pin "2") (pinfunction "2_2") (pintype "passive"))
      (node (ref "R6") (pin "1") (pinfunction "1_1") (pintype "passive"))
    )
    (net (code "59") (name "Net-(C15-Pad2)") (class "Default")
      (node (ref "C15") (pin "2") (pinfunction "2_2") (pintype "passive"))
      (node (ref "R7") (pin "1") (pinfunction "1_1") (pintype "passive"))
    )
    (net (code "60") (name "Net-(C18-Pad2)") (class "Default")
      (node (ref "C18") (pin "2") (pinfunction "2_2") (pintype "passive"))
      (node (ref "R8") (pin "1") (pinfunction "1_1") (pintype "passive"))
    )
    (net (code "61") (name "Net-(D1-PadA)") (class "Default")
      (node (ref "D1") (pin "A") (pinfunction "A_A") (pintype "passive"))
      (node (ref "Q1") (pin "S") (pinfunction "S_S") (pintype "bidirectional"))
      (node (ref "R3") (pin "2") (pinfunction "2_2") (pintype "passive"))
    )
    (net (code "62") (name "Net-(D1-PadC)") (class "Default")
      (node (ref "D1") (pin "C") (pinfunction "C_C") (pintype "passive"))
      (node (ref "Q1") (pin "G") (pinfunction "G_G") (pintype "bidirectional"))
      (node (ref "R15") (pin "2") (pinfunction "2_2") (pintype "passive"))
    )
    (net (code "63") (name "Net-(D2-PadA)") (class "Default")
      (node (ref "D2") (pin "A") (pinfunction "A_A") (pintype "passive"))
      (node (ref "Q2") (pin "S") (pinfunction "S_S") (pintype "bidirectional"))
      (node (ref "R5") (pin "2") (pinfunction "2_2") (pintype "passive"))
    )
    (net (code "64") (name "Net-(D2-PadC)") (class "Default")
      (node (ref "D2") (pin "C") (pinfunction "C_C") (pintype "passive"))
      (node (ref "Q2") (pin "G") (pinfunction "G_G") (pintype "bidirectional"))
      (node (ref "R16") (pin "2") (pinfunction "2_2") (pintype "passive"))
    )
    (net (code "65") (name "Net-(LED1+-Pad1)") (class "Default")
      (node (ref "LED1") (pin "A1") (pinfunction "A_A1") (pintype "passive"))
      (node (ref "LED1") (pin "A2") (pinfunction "A_A2") (pintype "passive"))
      (node (ref "LED1+") (pin "1") (pinfunction "1_1") (pintype "passive"))
      (node (ref "R3") (pin "1") (pinfunction "1_1") (pintype "passive"))
    )
    (net (code "66") (name "Net-(LED2+-Pad1)") (class "Default")
      (node (ref "LED2") (pin "A1") (pinfunction "A_A1") (pintype "passive"))
      (node (ref "LED2") (pin "A2") (pinfunction "A_A2") (pintype "passive"))
      (node (ref "LED2+") (pin "1") (pinfunction "1_1") (pintype "passive"))
      (node (ref "R5") (pin "1") (pinfunction "1_1") (pintype "passive"))
    )
    (net (code "67") (name "Net-(R2-A)") (class "Default")
      (node (ref "R-A") (pin "1") (pinfunction "1_1") (pintype "passive"))
      (node (ref "R2") (pin "1") (pinfunction "A_1") (pintype "passive"))
      (node (ref "RIGHT") (pin "A1") (pinfunction "A_A1") (pintype "passive"))
      (node (ref "RIGHT") (pin "A2") (pinfunction "A_A2") (pintype "passive"))
    )
    (net (code "68") (name "Net-(R4-A)") (class "Default")
      (node (ref "L-A") (pin "1") (pinfunction "1_1") (pintype "passive"))
      (node (ref "LEFT") (pin "A1") (pinfunction "A_A1") (pintype "passive"))
      (node (ref "LEFT") (pin "A2") (pinfunction "A_A2") (pintype "passive"))
      (node (ref "R4") (pin "1") (pinfunction "A_1") (pintype "passive"))
    )
    (net (code "69") (name "Net-(R15-Pad1)") (class "Default")
      (node (ref "R15") (pin "1") (pinfunction "1_1") (pintype "passive"))
      (node (ref "R16") (pin "1") (pinfunction "1_1") (pintype "passive"))
      (node (ref "U107") (pin "6") (pinfunction "VO_6") (pintype "bidirectional"))
      (node (ref "U107") (pin "7") (pinfunction "VO_7") (pintype "bidirectional"))
    )
    (net (code "70") (name "Net-(U1-VCONT)") (class "Default")
      (node (ref "C11") (pin "1") (pinfunction "1_1") (pintype "passive"))
      (node (ref "C12") (pin "1") (pinfunction "1_1") (pintype "passive"))
      (node (ref "U1") (pin "3") (pinfunction "VCONT_3") (pintype "passive"))
    )
    (net (code "71") (name "Net-(U2-VCONT)") (class "Default")
      (node (ref "C14") (pin "1") (pinfunction "1_1") (pintype "passive"))
      (node (ref "C15") (pin "1") (pinfunction "1_1") (pintype "passive"))
      (node (ref "U2") (pin "3") (pinfunction "VCONT_3") (pintype "passive"))
    )
    (net (code "72") (name "Net-(U3-VCONT)") (class "Default")
      (node (ref "C17") (pin "1") (pinfunction "1_1") (pintype "passive"))
      (node (ref "C18") (pin "1") (pinfunction "1_1") (pintype "passive"))
      (node (ref "U3") (pin "3") (pinfunction "VCONT_3") (pintype "passive"))
    )
    (net (code "73") (name "Net-(U100-~{PD2})") (class "Default")
      (node (ref "R9") (pin "2") (pinfunction "2_2") (pintype "passive"))
      (node (ref "U100") (pin "4") (pinfunction "~{PD2}_4") (pintype "passive"))
    )
    (net (code "74") (name "Net-(U101-~{PD2})") (class "Default")
      (node (ref "R10") (pin "2") (pinfunction "2_2") (pintype "passive"))
      (node (ref "U101") (pin "4") (pinfunction "~{PD2}_4") (pintype "passive"))
    )
    (net (code "75") (name "Net-(U102-~{PD2})") (class "Default")
      (node (ref "R11") (pin "2") (pinfunction "2_2") (pintype "passive"))
      (node (ref "U102") (pin "4") (pinfunction "~{PD2}_4") (pintype "passive"))
    )
    (net (code "76") (name "Net-(U106-Y)") (class "Default")
      (node (ref "R1") (pin "1") (pinfunction "1_1") (pintype "passive"))
      (node (ref "U106") (pin "4") (pinfunction "Y_4") (pintype "output"))
    )
    (net (code "77") (name "Net-(U107-A)") (class "Default")
      (node (ref "R1") (pin "2") (pinfunction "2_2") (pintype "passive"))
      (node (ref "U107") (pin "2") (pinfunction "A_2") (pintype "bidirectional"))
    )
    (net (code "78") (name "VCC") (class "Default")
      (node (ref "C1") (pin "2") (pinfunction "2_2") (pintype "passive"))
      (node (ref "C13") (pin "1") (pinfunction "1_1") (pintype "passive"))
      (node (ref "C16") (pin "1") (pinfunction "1_1") (pintype "passive"))
      (node (ref "C19") (pin "1") (pinfunction "1_1") (pintype "passive"))
      (node (ref "C2") (pin "1") (pinfunction "1_1") (pintype "passive"))
      (node (ref "C20") (pin "1") (pinfunction "1_1") (pintype "passive"))
      (node (ref "C24") (pin "2") (pinfunction "2_2") (pintype "passive"))
      (node (ref "C3") (pin "1") (pinfunction "1_1") (pintype "passive"))
      (node (ref "C4") (pin "1") (pinfunction "1_1") (pintype "passive"))
      (node (ref "C5") (pin "1") (pinfunction "1_1") (pintype "passive"))
      (node (ref "C6") (pin "1") (pinfunction "1_1") (pintype "passive"))
      (node (ref "C7") (pin "1") (pinfunction "1_1") (pintype "passive"))
      (node (ref "C8") (pin "1") (pinfunction "1_1") (pintype "passive"))
      (node (ref "DIO_E1B") (pin "10") (pinfunction "10_10") (pintype "bidirectional"))
      (node (ref "DIO_E1B1") (pin "10") (pinfunction "10_10") (pintype "bidirectional"))
      (node (ref "R10") (pin "1") (pinfunction "1_1") (pintype "passive"))
      (node (ref "R11") (pin "1") (pinfunction "1_1") (pintype "passive"))
      (node (ref "R2") (pin "2") (pinfunction "W_2") (pintype "passive"))
      (node (ref "R2") (pin "3") (pinfunction "E_3") (pintype "passive"))
      (node (ref "R4") (pin "2") (pinfunction "W_2") (pintype "passive"))
      (node (ref "R4") (pin "3") (pinfunction "E_3") (pintype "passive"))
      (node (ref "R9") (pin "1") (pinfunction "1_1") (pintype "passive"))
      (node (ref "TETHER") (pin "12") (pinfunction "12_12") (pintype "bidirectional"))
      (node (ref "TP1") (pin "1") (pinfunction "1_1") (pintype "passive"))
      (node (ref "TP2") (pin "1") (pinfunction "1_1") (pintype "passive"))
      (node (ref "TP3") (pin "TP") (pinfunction "TP_TP") (pintype "input"))
      (node (ref "TP9") (pin "TP") (pinfunction "TP_TP") (pintype "input"))
      (node (ref "U1") (pin "1") (pinfunction "VDD_1") (pintype "power_in"))
      (node (ref "U1") (pin "10") (pinfunction "RES1_10") (pintype "passive"))
      (node (ref "U1") (pin "9") (pinfunction "VDD_9") (pintype "power_in"))
      (node (ref "U100") (pin "5") (pinfunction "~{PD1}_5") (pintype "passive"))
      (node (ref "U100") (pin "8") (pinfunction "VCC_8") (pintype "power_in"))
      (node (ref "U101") (pin "5") (pinfunction "~{PD1}_5") (pintype "passive"))
      (node (ref "U101") (pin "8") (pinfunction "VCC_8") (pintype "power_in"))
      (node (ref "U102") (pin "5") (pinfunction "~{PD1}_5") (pintype "passive"))
      (node (ref "U102") (pin "8") (pinfunction "VCC_8") (pintype "power_in"))
      (node (ref "U106") (pin "5") (pinfunction "VCC_5") (pintype "power_in"))
      (node (ref "U13") (pin "VCC") (pinfunction "VCC_VCC") (pintype "power_in"))
      (node (ref "U14") (pin "VCC") (pinfunction "VCC_VCC") (pintype "power_in"))
      (node (ref "U2") (pin "1") (pinfunction "VDD_1") (pintype "power_in"))
      (node (ref "U2") (pin "10") (pinfunction "RES1_10") (pintype "passive"))
      (node (ref "U2") (pin "9") (pinfunction "VDD_9") (pintype "power_in"))
      (node (ref "U3") (pin "1") (pinfunction "VDD_1") (pintype "power_in"))
      (node (ref "U3") (pin "10") (pinfunction "RES1_10") (pintype "passive"))
      (node (ref "U3") (pin "9") (pinfunction "VDD_9") (pintype "power_in"))
      (node (ref "U4") (pin "VS1") (pinfunction "VS1_VS1") (pintype "bidirectional"))
      (node (ref "U4") (pin "VS2") (pinfunction "VS2_VS2") (pintype "bidirectional"))
    )
    (net (code "79") (name "unconnected-(MECH_E0B-Pad1)") (class "Default")
      (node (ref "MECH_E0B") (pin "1") (pinfunction "1_1") (pintype "bidirectional"))
    )
    (net (code "80") (name "unconnected-(MECH_E0B-Pad2)") (class "Default")
      (node (ref "MECH_E0B") (pin "2") (pinfunction "2_2") (pintype "bidirectional"))
    )
    (net (code "81") (name "unconnected-(MECH_E0B-Pad3)") (class "Default")
      (node (ref "MECH_E0B") (pin "3") (pinfunction "3_3") (pintype "bidirectional"))
    )
    (net (code "82") (name "unconnected-(MECH_E0B-Pad4)") (class "Default")
      (node (ref "MECH_E0B") (pin "4") (pinfunction "4_4") (pintype "bidirectional"))
    )
    (net (code "83") (name "unconnected-(MECH_E0B-Pad5)") (class "Default")
      (node (ref "MECH_E0B") (pin "5") (pinfunction "5_5") (pintype "bidirectional"))
    )
    (net (code "84") (name "unconnected-(MECH_E0B-Pad6)") (class "Default")
      (node (ref "MECH_E0B") (pin "6") (pinfunction "6_6") (pintype "bidirectional"))
    )
    (net (code "85") (name "unconnected-(MECH_E0B-Pad7)") (class "Default")
      (node (ref "MECH_E0B") (pin "7") (pinfunction "7_7") (pintype "bidirectional"))
    )
    (net (code "86") (name "unconnected-(MECH_E0B-Pad8)") (class "Default")
      (node (ref "MECH_E0B") (pin "8") (pinfunction "8_8") (pintype "bidirectional"))
    )
    (net (code "87") (name "unconnected-(MECH_E0B-Pad9)") (class "Default")
      (node (ref "MECH_E0B") (pin "9") (pinfunction "9_9") (pintype "bidirectional"))
    )
    (net (code "88") (name "unconnected-(MECH_E0B-Pad10)") (class "Default")
      (node (ref "MECH_E0B") (pin "10") (pinfunction "10_10") (pintype "bidirectional"))
    )
    (net (code "89") (name "unconnected-(MECH_E0B-Pad11)") (class "Default")
      (node (ref "MECH_E0B") (pin "11") (pinfunction "11_11") (pintype "bidirectional"))
    )
    (net (code "90") (name "unconnected-(MECH_E0B-Pad12)") (class "Default")
      (node (ref "MECH_E0B") (pin "12") (pinfunction "12_12") (pintype "bidirectional"))
    )
    (net (code "91") (name "unconnected-(MECH_E0B-Pad13)") (class "Default")
      (node (ref "MECH_E0B") (pin "13") (pinfunction "13_13") (pintype "bidirectional"))
    )
    (net (code "92") (name "unconnected-(MECH_E0B-Pad14)") (class "Default")
      (node (ref "MECH_E0B") (pin "14") (pinfunction "14_14") (pintype "bidirectional"))
    )
    (net (code "93") (name "unconnected-(MECH_E0B-Pad15)") (class "Default")
      (node (ref "MECH_E0B") (pin "15") (pinfunction "15_15") (pintype "bidirectional"))
    )
    (net (code "94") (name "unconnected-(MECH_E0B-Pad16)") (class "Default")
      (node (ref "MECH_E0B") (pin "16") (pinfunction "16_16") (pintype "bidirectional"))
    )
    (net (code "95") (name "unconnected-(MECH_E0B-Pad17)") (class "Default")
      (node (ref "MECH_E0B") (pin "17") (pinfunction "17_17") (pintype "bidirectional"))
    )
    (net (code "96") (name "unconnected-(MECH_E0B-Pad18)") (class "Default")
      (node (ref "MECH_E0B") (pin "18") (pinfunction "18_18") (pintype "bidirectional"))
    )
    (net (code "97") (name "unconnected-(MECH_E0B-Pad19)") (class "Default")
      (node (ref "MECH_E0B") (pin "19") (pinfunction "19_19") (pintype "bidirectional"))
    )
    (net (code "98") (name "unconnected-(MECH_E0B-Pad20)") (class "Default")
      (node (ref "MECH_E0B") (pin "20") (pinfunction "20_20") (pintype "bidirectional"))
    )
    (net (code "99") (name "unconnected-(MECH_E0B-Pad21)") (class "Default")
      (node (ref "MECH_E0B") (pin "21") (pinfunction "21_21") (pintype "bidirectional"))
    )
    (net (code "100") (name "unconnected-(MECH_E0B-Pad22)") (class "Default")
      (node (ref "MECH_E0B") (pin "22") (pinfunction "22_22") (pintype "bidirectional"))
    )
    (net (code "101") (name "unconnected-(MECH_E0B-Pad23)") (class "Default")
      (node (ref "MECH_E0B") (pin "23") (pinfunction "23_23") (pintype "bidirectional"))
    )
    (net (code "102") (name "unconnected-(MECH_E0B-Pad24)") (class "Default")
      (node (ref "MECH_E0B") (pin "24") (pinfunction "24_24") (pintype "bidirectional"))
    )
    (net (code "103") (name "unconnected-(MECH_E0B-Pad25)") (class "Default")
      (node (ref "MECH_E0B") (pin "25") (pinfunction "25_25") (pintype "bidirectional"))
    )
    (net (code "104") (name "unconnected-(MECH_E0B-Pad26)") (class "Default")
      (node (ref "MECH_E0B") (pin "26") (pinfunction "26_26") (pintype "bidirectional"))
    )
    (net (code "105") (name "unconnected-(MECH_E0B-Pad27)") (class "Default")
      (node (ref "MECH_E0B") (pin "27") (pinfunction "27_27") (pintype "bidirectional"))
    )
    (net (code "106") (name "unconnected-(MECH_E0B-Pad28)") (class "Default")
      (node (ref "MECH_E0B") (pin "28") (pinfunction "28_28") (pintype "bidirectional"))
    )
    (net (code "107") (name "unconnected-(MECH_E0B-Pad29)") (class "Default")
      (node (ref "MECH_E0B") (pin "29") (pinfunction "29_29") (pintype "bidirectional"))
    )
    (net (code "108") (name "unconnected-(MECH_E0B-Pad30)") (class "Default")
      (node (ref "MECH_E0B") (pin "30") (pinfunction "30_30") (pintype "bidirectional"))
    )
    (net (code "109") (name "unconnected-(MECH_E0B-Pad31)") (class "Default")
      (node (ref "MECH_E0B") (pin "31") (pinfunction "31_31") (pintype "bidirectional"))
    )
    (net (code "110") (name "unconnected-(MECH_E0B-Pad32)") (class "Default")
      (node (ref "MECH_E0B") (pin "32") (pinfunction "32_32") (pintype "bidirectional"))
    )
    (net (code "111") (name "unconnected-(MECH_E0B-Pad33)") (class "Default")
      (node (ref "MECH_E0B") (pin "33") (pinfunction "33_33") (pintype "bidirectional"))
    )
    (net (code "112") (name "unconnected-(MECH_E0B-Pad34)") (class "Default")
      (node (ref "MECH_E0B") (pin "34") (pinfunction "34_34") (pintype "bidirectional"))
    )
    (net (code "113") (name "unconnected-(MECH_E0B-Pad35)") (class "Default")
      (node (ref "MECH_E0B") (pin "35") (pinfunction "35_35") (pintype "bidirectional"))
    )
    (net (code "114") (name "unconnected-(MECH_E0B-Pad36)") (class "Default")
      (node (ref "MECH_E0B") (pin "36") (pinfunction "36_36") (pintype "bidirectional"))
    )
    (net (code "115") (name "unconnected-(MECH_E0B-Pad37)") (class "Default")
      (node (ref "MECH_E0B") (pin "37") (pinfunction "37_37") (pintype "bidirectional"))
    )
    (net (code "116") (name "unconnected-(MECH_E0B-Pad38)") (class "Default")
      (node (ref "MECH_E0B") (pin "38") (pinfunction "38_38") (pintype "bidirectional"))
    )
    (net (code "117") (name "unconnected-(MECH_E0B-Pad39)") (class "Default")
      (node (ref "MECH_E0B") (pin "39") (pinfunction "39_39") (pintype "bidirectional"))
    )
    (net (code "118") (name "unconnected-(MECH_E0B-Pad40)") (class "Default")
      (node (ref "MECH_E0B") (pin "40") (pinfunction "40_40") (pintype "bidirectional"))
    )
    (net (code "119") (name "unconnected-(MECH_E0B-Pad41)") (class "Default")
      (node (ref "MECH_E0B") (pin "41") (pinfunction "41_41") (pintype "bidirectional"))
    )
    (net (code "120") (name "unconnected-(MECH_E0B-Pad42)") (class "Default")
      (node (ref "MECH_E0B") (pin "42") (pinfunction "42_42") (pintype "bidirectional"))
    )
    (net (code "121") (name "unconnected-(MECH_E0B-Pad43)") (class "Default")
      (node (ref "MECH_E0B") (pin "43") (pinfunction "43_43") (pintype "bidirectional"))
    )
    (net (code "122") (name "unconnected-(MECH_E0B-Pad44)") (class "Default")
      (node (ref "MECH_E0B") (pin "44") (pinfunction "44_44") (pintype "bidirectional"))
    )
    (net (code "123") (name "unconnected-(MECH_E0B-Pad45)") (class "Default")
      (node (ref "MECH_E0B") (pin "45") (pinfunction "45_45") (pintype "bidirectional"))
    )
    (net (code "124") (name "unconnected-(MECH_E0B-Pad46)") (class "Default")
      (node (ref "MECH_E0B") (pin "46") (pinfunction "46_46") (pintype "bidirectional"))
    )
    (net (code "125") (name "unconnected-(MECH_E0B-Pad47)") (class "Default")
      (node (ref "MECH_E0B") (pin "47") (pinfunction "47_47") (pintype "bidirectional"))
    )
    (net (code "126") (name "unconnected-(MECH_E0B-Pad48)") (class "Default")
      (node (ref "MECH_E0B") (pin "48") (pinfunction "48_48") (pintype "bidirectional"))
    )
    (net (code "127") (name "unconnected-(MECH_E0B-Pad49)") (class "Default")
      (node (ref "MECH_E0B") (pin "49") (pinfunction "49_49") (pintype "bidirectional"))
    )
    (net (code "128") (name "unconnected-(MECH_E0B-Pad50)") (class "Default")
      (node (ref "MECH_E0B") (pin "50") (pinfunction "50_50") (pintype "bidirectional"))
    )
    (net (code "129") (name "unconnected-(MECH_E0B-Pad51)") (class "Default")
      (node (ref "MECH_E0B") (pin "51") (pinfunction "51_51") (pintype "bidirectional"))
    )
    (net (code "130") (name "unconnected-(MECH_E0B-Pad52)") (class "Default")
      (node (ref "MECH_E0B") (pin "52") (pinfunction "52_52") (pintype "bidirectional"))
    )
    (net (code "131") (name "unconnected-(MECH_E0B-Pad53)") (class "Default")
      (node (ref "MECH_E0B") (pin "53") (pinfunction "53_53") (pintype "bidirectional"))
    )
    (net (code "132") (name "unconnected-(MECH_E0B-Pad54)") (class "Default")
      (node (ref "MECH_E0B") (pin "54") (pinfunction "54_54") (pintype "bidirectional"))
    )
    (net (code "133") (name "unconnected-(MECH_E0B-Pad55)") (class "Default")
      (node (ref "MECH_E0B") (pin "55") (pinfunction "55_55") (pintype "bidirectional"))
    )
    (net (code "134") (name "unconnected-(MECH_E0B-Pad56)") (class "Default")
      (node (ref "MECH_E0B") (pin "56") (pinfunction "56_56") (pintype "bidirectional"))
    )
    (net (code "135") (name "unconnected-(MECH_E0B-Pad57)") (class "Default")
      (node (ref "MECH_E0B") (pin "57") (pinfunction "57_57") (pintype "bidirectional"))
    )
    (net (code "136") (name "unconnected-(MECH_E0B-Pad58)") (class "Default")
      (node (ref "MECH_E0B") (pin "58") (pinfunction "58_58") (pintype "bidirectional"))
    )
    (net (code "137") (name "unconnected-(MECH_E0B-Pad59)") (class "Default")
      (node (ref "MECH_E0B") (pin "59") (pinfunction "59_59") (pintype "bidirectional"))
    )
    (net (code "138") (name "unconnected-(MECH_E0B-Pad60)") (class "Default")
      (node (ref "MECH_E0B") (pin "60") (pinfunction "60_60") (pintype "bidirectional"))
    )
    (net (code "139") (name "unconnected-(MECH_E0B-Pad61)") (class "Default")
      (node (ref "MECH_E0B") (pin "61") (pinfunction "61_61") (pintype "bidirectional"))
    )
    (net (code "140") (name "unconnected-(MECH_E0B-Pad62)") (class "Default")
      (node (ref "MECH_E0B") (pin "62") (pinfunction "62_62") (pintype "bidirectional"))
    )
    (net (code "141") (name "unconnected-(MECH_E0B-Pad63)") (class "Default")
      (node (ref "MECH_E0B") (pin "63") (pinfunction "63_63") (pintype "bidirectional"))
    )
    (net (code "142") (name "unconnected-(MECH_E0B-Pad64)") (class "Default")
      (node (ref "MECH_E0B") (pin "64") (pinfunction "64_64") (pintype "bidirectional"))
    )
    (net (code "143") (name "unconnected-(MECH_E0B-Pad65)") (class "Default")
      (node (ref "MECH_E0B") (pin "65") (pinfunction "65_65") (pintype "bidirectional"))
    )
    (net (code "144") (name "unconnected-(MECH_E0B-Pad66)") (class "Default")
      (node (ref "MECH_E0B") (pin "66") (pinfunction "66_66") (pintype "bidirectional"))
    )
    (net (code "145") (name "unconnected-(MECH_E0B-Pad67)") (class "Default")
      (node (ref "MECH_E0B") (pin "67") (pinfunction "67_67") (pintype "bidirectional"))
    )
    (net (code "146") (name "unconnected-(MECH_E0B-Pad68)") (class "Default")
      (node (ref "MECH_E0B") (pin "68") (pinfunction "68_68") (pintype "bidirectional"))
    )
    (net (code "147") (name "unconnected-(MECH_E0B-Pad69)") (class "Default")
      (node (ref "MECH_E0B") (pin "69") (pinfunction "69_69") (pintype "bidirectional"))
    )
    (net (code "148") (name "unconnected-(MECH_E0B-Pad70)") (class "Default")
      (node (ref "MECH_E0B") (pin "70") (pinfunction "70_70") (pintype "bidirectional"))
    )
    (net (code "149") (name "unconnected-(MECH_W0B-Pad1)") (class "Default")
      (node (ref "MECH_W0B") (pin "1") (pinfunction "1_1") (pintype "bidirectional"))
    )
    (net (code "150") (name "unconnected-(MECH_W0B-Pad2)") (class "Default")
      (node (ref "MECH_W0B") (pin "2") (pinfunction "2_2") (pintype "bidirectional"))
    )
    (net (code "151") (name "unconnected-(MECH_W0B-Pad3)") (class "Default")
      (node (ref "MECH_W0B") (pin "3") (pinfunction "3_3") (pintype "bidirectional"))
    )
    (net (code "152") (name "unconnected-(MECH_W0B-Pad4)") (class "Default")
      (node (ref "MECH_W0B") (pin "4") (pinfunction "4_4") (pintype "bidirectional"))
    )
    (net (code "153") (name "unconnected-(MECH_W0B-Pad5)") (class "Default")
      (node (ref "MECH_W0B") (pin "5") (pinfunction "5_5") (pintype "bidirectional"))
    )
    (net (code "154") (name "unconnected-(MECH_W0B-Pad6)") (class "Default")
      (node (ref "MECH_W0B") (pin "6") (pinfunction "6_6") (pintype "bidirectional"))
    )
    (net (code "155") (name "unconnected-(MECH_W0B-Pad7)") (class "Default")
      (node (ref "MECH_W0B") (pin "7") (pinfunction "7_7") (pintype "bidirectional"))
    )
    (net (code "156") (name "unconnected-(MECH_W0B-Pad8)") (class "Default")
      (node (ref "MECH_W0B") (pin "8") (pinfunction "8_8") (pintype "bidirectional"))
    )
    (net (code "157") (name "unconnected-(MECH_W0B-Pad9)") (class "Default")
      (node (ref "MECH_W0B") (pin "9") (pinfunction "9_9") (pintype "bidirectional"))
    )
    (net (code "158") (name "unconnected-(MECH_W0B-Pad10)") (class "Default")
      (node (ref "MECH_W0B") (pin "10") (pinfunction "10_10") (pintype "bidirectional"))
    )
    (net (code "159") (name "unconnected-(MECH_W0B-Pad11)") (class "Default")
      (node (ref "MECH_W0B") (pin "11") (pinfunction "11_11") (pintype "bidirectional"))
    )
    (net (code "160") (name "unconnected-(MECH_W0B-Pad12)") (class "Default")
      (node (ref "MECH_W0B") (pin "12") (pinfunction "12_12") (pintype "bidirectional"))
    )
    (net (code "161") (name "unconnected-(MECH_W0B-Pad13)") (class "Default")
      (node (ref "MECH_W0B") (pin "13") (pinfunction "13_13") (pintype "bidirectional"))
    )
    (net (code "162") (name "unconnected-(MECH_W0B-Pad14)") (class "Default")
      (node (ref "MECH_W0B") (pin "14") (pinfunction "14_14") (pintype "bidirectional"))
    )
    (net (code "163") (name "unconnected-(MECH_W0B-Pad15)") (class "Default")
      (node (ref "MECH_W0B") (pin "15") (pinfunction "15_15") (pintype "bidirectional"))
    )
    (net (code "164") (name "unconnected-(MECH_W0B-Pad16)") (class "Default")
      (node (ref "MECH_W0B") (pin "16") (pinfunction "16_16") (pintype "bidirectional"))
    )
    (net (code "165") (name "unconnected-(MECH_W0B-Pad17)") (class "Default")
      (node (ref "MECH_W0B") (pin "17") (pinfunction "17_17") (pintype "bidirectional"))
    )
    (net (code "166") (name "unconnected-(MECH_W0B-Pad18)") (class "Default")
      (node (ref "MECH_W0B") (pin "18") (pinfunction "18_18") (pintype "bidirectional"))
    )
    (net (code "167") (name "unconnected-(MECH_W0B-Pad19)") (class "Default")
      (node (ref "MECH_W0B") (pin "19") (pinfunction "19_19") (pintype "bidirectional"))
    )
    (net (code "168") (name "unconnected-(MECH_W0B-Pad20)") (class "Default")
      (node (ref "MECH_W0B") (pin "20") (pinfunction "20_20") (pintype "bidirectional"))
    )
    (net (code "169") (name "unconnected-(MECH_W0B-Pad21)") (class "Default")
      (node (ref "MECH_W0B") (pin "21") (pinfunction "21_21") (pintype "bidirectional"))
    )
    (net (code "170") (name "unconnected-(MECH_W0B-Pad22)") (class "Default")
      (node (ref "MECH_W0B") (pin "22") (pinfunction "22_22") (pintype "bidirectional"))
    )
    (net (code "171") (name "unconnected-(MECH_W0B-Pad23)") (class "Default")
      (node (ref "MECH_W0B") (pin "23") (pinfunction "23_23") (pintype "bidirectional"))
    )
    (net (code "172") (name "unconnected-(MECH_W0B-Pad24)") (class "Default")
      (node (ref "MECH_W0B") (pin "24") (pinfunction "24_24") (pintype "bidirectional"))
    )
    (net (code "173") (name "unconnected-(MECH_W0B-Pad25)") (class "Default")
      (node (ref "MECH_W0B") (pin "25") (pinfunction "25_25") (pintype "bidirectional"))
    )
    (net (code "174") (name "unconnected-(MECH_W0B-Pad26)") (class "Default")
      (node (ref "MECH_W0B") (pin "26") (pinfunction "26_26") (pintype "bidirectional"))
    )
    (net (code "175") (name "unconnected-(MECH_W0B-Pad27)") (class "Default")
      (node (ref "MECH_W0B") (pin "27") (pinfunction "27_27") (pintype "bidirectional"))
    )
    (net (code "176") (name "unconnected-(MECH_W0B-Pad28)") (class "Default")
      (node (ref "MECH_W0B") (pin "28") (pinfunction "28_28") (pintype "bidirectional"))
    )
    (net (code "177") (name "unconnected-(MECH_W0B-Pad29)") (class "Default")
      (node (ref "MECH_W0B") (pin "29") (pinfunction "29_29") (pintype "bidirectional"))
    )
    (net (code "178") (name "unconnected-(MECH_W0B-Pad30)") (class "Default")
      (node (ref "MECH_W0B") (pin "30") (pinfunction "30_30") (pintype "bidirectional"))
    )
    (net (code "179") (name "unconnected-(MECH_W0B-Pad31)") (class "Default")
      (node (ref "MECH_W0B") (pin "31") (pinfunction "31_31") (pintype "bidirectional"))
    )
    (net (code "180") (name "unconnected-(MECH_W0B-Pad32)") (class "Default")
      (node (ref "MECH_W0B") (pin "32") (pinfunction "32_32") (pintype "bidirectional"))
    )
    (net (code "181") (name "unconnected-(MECH_W0B-Pad33)") (class "Default")
      (node (ref "MECH_W0B") (pin "33") (pinfunction "33_33") (pintype "bidirectional"))
    )
    (net (code "182") (name "unconnected-(MECH_W0B-Pad34)") (class "Default")
      (node (ref "MECH_W0B") (pin "34") (pinfunction "34_34") (pintype "bidirectional"))
    )
    (net (code "183") (name "unconnected-(MECH_W0B-Pad35)") (class "Default")
      (node (ref "MECH_W0B") (pin "35") (pinfunction "35_35") (pintype "bidirectional"))
    )
    (net (code "184") (name "unconnected-(MECH_W0B-Pad36)") (class "Default")
      (node (ref "MECH_W0B") (pin "36") (pinfunction "36_36") (pintype "bidirectional"))
    )
    (net (code "185") (name "unconnected-(MECH_W0B-Pad37)") (class "Default")
      (node (ref "MECH_W0B") (pin "37") (pinfunction "37_37") (pintype "bidirectional"))
    )
    (net (code "186") (name "unconnected-(MECH_W0B-Pad38)") (class "Default")
      (node (ref "MECH_W0B") (pin "38") (pinfunction "38_38") (pintype "bidirectional"))
    )
    (net (code "187") (name "unconnected-(MECH_W0B-Pad39)") (class "Default")
      (node (ref "MECH_W0B") (pin "39") (pinfunction "39_39") (pintype "bidirectional"))
    )
    (net (code "188") (name "unconnected-(MECH_W0B-Pad40)") (class "Default")
      (node (ref "MECH_W0B") (pin "40") (pinfunction "40_40") (pintype "bidirectional"))
    )
    (net (code "189") (name "unconnected-(MECH_W0B-Pad41)") (class "Default")
      (node (ref "MECH_W0B") (pin "41") (pinfunction "41_41") (pintype "bidirectional"))
    )
    (net (code "190") (name "unconnected-(MECH_W0B-Pad42)") (class "Default")
      (node (ref "MECH_W0B") (pin "42") (pinfunction "42_42") (pintype "bidirectional"))
    )
    (net (code "191") (name "unconnected-(MECH_W0B-Pad43)") (class "Default")
      (node (ref "MECH_W0B") (pin "43") (pinfunction "43_43") (pintype "bidirectional"))
    )
    (net (code "192") (name "unconnected-(MECH_W0B-Pad44)") (class "Default")
      (node (ref "MECH_W0B") (pin "44") (pinfunction "44_44") (pintype "bidirectional"))
    )
    (net (code "193") (name "unconnected-(MECH_W0B-Pad45)") (class "Default")
      (node (ref "MECH_W0B") (pin "45") (pinfunction "45_45") (pintype "bidirectional"))
    )
    (net (code "194") (name "unconnected-(MECH_W0B-Pad46)") (class "Default")
      (node (ref "MECH_W0B") (pin "46") (pinfunction "46_46") (pintype "bidirectional"))
    )
    (net (code "195") (name "unconnected-(MECH_W0B-Pad47)") (class "Default")
      (node (ref "MECH_W0B") (pin "47") (pinfunction "47_47") (pintype "bidirectional"))
    )
    (net (code "196") (name "unconnected-(MECH_W0B-Pad48)") (class "Default")
      (node (ref "MECH_W0B") (pin "48") (pinfunction "48_48") (pintype "bidirectional"))
    )
    (net (code "197") (name "unconnected-(MECH_W0B-Pad49)") (class "Default")
      (node (ref "MECH_W0B") (pin "49") (pinfunction "49_49") (pintype "bidirectional"))
    )
    (net (code "198") (name "unconnected-(MECH_W0B-Pad50)") (class "Default")
      (node (ref "MECH_W0B") (pin "50") (pinfunction "50_50") (pintype "bidirectional"))
    )
    (net (code "199") (name "unconnected-(MECH_W0B-Pad51)") (class "Default")
      (node (ref "MECH_W0B") (pin "51") (pinfunction "51_51") (pintype "bidirectional"))
    )
    (net (code "200") (name "unconnected-(MECH_W0B-Pad52)") (class "Default")
      (node (ref "MECH_W0B") (pin "52") (pinfunction "52_52") (pintype "bidirectional"))
    )
    (net (code "201") (name "unconnected-(MECH_W0B-Pad53)") (class "Default")
      (node (ref "MECH_W0B") (pin "53") (pinfunction "53_53") (pintype "bidirectional"))
    )
    (net (code "202") (name "unconnected-(MECH_W0B-Pad54)") (class "Default")
      (node (ref "MECH_W0B") (pin "54") (pinfunction "54_54") (pintype "bidirectional"))
    )
    (net (code "203") (name "unconnected-(MECH_W0B-Pad55)") (class "Default")
      (node (ref "MECH_W0B") (pin "55") (pinfunction "55_55") (pintype "bidirectional"))
    )
    (net (code "204") (name "unconnected-(MECH_W0B-Pad56)") (class "Default")
      (node (ref "MECH_W0B") (pin "56") (pinfunction "56_56") (pintype "bidirectional"))
    )
    (net (code "205") (name "unconnected-(MECH_W0B-Pad57)") (class "Default")
      (node (ref "MECH_W0B") (pin "57") (pinfunction "57_57") (pintype "bidirectional"))
    )
    (net (code "206") (name "unconnected-(MECH_W0B-Pad58)") (class "Default")
      (node (ref "MECH_W0B") (pin "58") (pinfunction "58_58") (pintype "bidirectional"))
    )
    (net (code "207") (name "unconnected-(MECH_W0B-Pad59)") (class "Default")
      (node (ref "MECH_W0B") (pin "59") (pinfunction "59_59") (pintype "bidirectional"))
    )
    (net (code "208") (name "unconnected-(MECH_W0B-Pad60)") (class "Default")
      (node (ref "MECH_W0B") (pin "60") (pinfunction "60_60") (pintype "bidirectional"))
    )
    (net (code "209") (name "unconnected-(MECH_W0B-Pad61)") (class "Default")
      (node (ref "MECH_W0B") (pin "61") (pinfunction "61_61") (pintype "bidirectional"))
    )
    (net (code "210") (name "unconnected-(MECH_W0B-Pad62)") (class "Default")
      (node (ref "MECH_W0B") (pin "62") (pinfunction "62_62") (pintype "bidirectional"))
    )
    (net (code "211") (name "unconnected-(MECH_W0B-Pad63)") (class "Default")
      (node (ref "MECH_W0B") (pin "63") (pinfunction "63_63") (pintype "bidirectional"))
    )
    (net (code "212") (name "unconnected-(MECH_W0B-Pad64)") (class "Default")
      (node (ref "MECH_W0B") (pin "64") (pinfunction "64_64") (pintype "bidirectional"))
    )
    (net (code "213") (name "unconnected-(MECH_W0B-Pad65)") (class "Default")
      (node (ref "MECH_W0B") (pin "65") (pinfunction "65_65") (pintype "bidirectional"))
    )
    (net (code "214") (name "unconnected-(MECH_W0B-Pad66)") (class "Default")
      (node (ref "MECH_W0B") (pin "66") (pinfunction "66_66") (pintype "bidirectional"))
    )
    (net (code "215") (name "unconnected-(MECH_W0B-Pad67)") (class "Default")
      (node (ref "MECH_W0B") (pin "67") (pinfunction "67_67") (pintype "bidirectional"))
    )
    (net (code "216") (name "unconnected-(MECH_W0B-Pad68)") (class "Default")
      (node (ref "MECH_W0B") (pin "68") (pinfunction "68_68") (pintype "bidirectional"))
    )
    (net (code "217") (name "unconnected-(MECH_W0B-Pad69)") (class "Default")
      (node (ref "MECH_W0B") (pin "69") (pinfunction "69_69") (pintype "bidirectional"))
    )
    (net (code "218") (name "unconnected-(MECH_W0B-Pad70)") (class "Default")
      (node (ref "MECH_W0B") (pin "70") (pinfunction "70_70") (pintype "bidirectional"))
    )
    (net (code "219") (name "unconnected-(U1-RES-Pad5)") (class "Default")
      (node (ref "U1") (pin "5") (pinfunction "RES_5") (pintype "passive"))
    )
    (net (code "220") (name "unconnected-(U2-RES-Pad5)") (class "Default")
      (node (ref "U2") (pin "5") (pinfunction "RES_5") (pintype "passive"))
    )
    (net (code "221") (name "unconnected-(U3-RES-Pad5)") (class "Default")
      (node (ref "U3") (pin "5") (pinfunction "RES_5") (pintype "passive"))
    )
    (net (code "222") (name "unconnected-(U4-PadNC1)") (class "Default")
      (node (ref "U4") (pin "NC1") (pinfunction "NC1_NC1") (pintype "bidirectional"))
    )
    (net (code "223") (name "unconnected-(U4-PadNC2)") (class "Default")
      (node (ref "U4") (pin "NC2") (pinfunction "NC2_NC2") (pintype "bidirectional"))
    )
    (net (code "224") (name "unconnected-(U4-PadNC3)") (class "Default")
      (node (ref "U4") (pin "NC3") (pinfunction "NC3_NC3") (pintype "bidirectional"))
    )
    (net (code "225") (name "unconnected-(U4-PadNC4)") (class "Default")
      (node (ref "U4") (pin "NC4") (pinfunction "NC4_NC4") (pintype "bidirectional"))
    )
    (net (code "226") (name "unconnected-(U4-PadNC5)") (class "Default")
      (node (ref "U4") (pin "NC5") (pinfunction "NC5_NC5") (pintype "bidirectional"))
    )
    (net (code "227") (name "unconnected-(U4-PadNC6)") (class "Default")
      (node (ref "U4") (pin "NC6") (pinfunction "NC6_NC6") (pintype "bidirectional"))
    )
  )
)
